# PowerSupply.net
KiCad netlist of a schematic drawn in Altium Designer
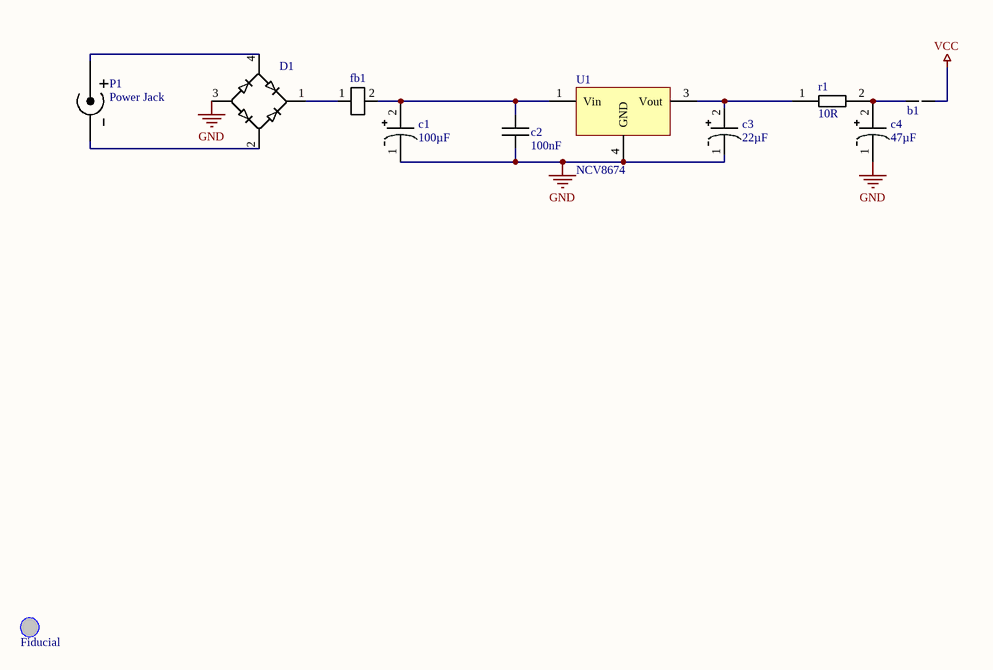
[diagram p0: PowerSupply.SchDoc]

(export (version "E")
  (design (tool "Eeschema 10.0.6"))
  (components
    (comp (ref "b1")
      (value "Solder Bridge")
      (footprint "Solder Bridge")
      (libsource (lib "Board_Props") (part "Solder Bridge"))
    )
    (comp (ref "c1")
      (value "100µF")
      (footprint "Elco-D")
      (description "Elco size D 6.3x5.4")
      (libsource (lib "Panasonic") (part "Elco D"))
    )
    (comp (ref "c2")
      (value "100nF")
      (footprint "0805")
      (description "...F")
      (libsource (lib "Generic R-C") (part "0805 Capacitor"))
    )
    (comp (ref "c3")
      (value "22µF")
      (footprint "Elco-D")
      (description "Elco size D 6.3x5.4")
      (libsource (lib "") (part "Elco D_1"))
    )
    (comp (ref "c4")
      (value "47µF")
      (footprint "Elco-D")
      (description "Elco size D 6.3x5.4")
      (libsource (lib "Panasonic") (part "Elco D"))
    )
    (comp (ref "D1")
      (value "Bridge Rectifier")
      (footprint "SOT-143")
      (libsource (lib "Infinion") (part "Bridge Rectifier"))
    )
    (comp (ref "f1")
      (value "Fiducial")
      (footprint "Fiducial")
      (libsource (lib "Board_Props") (part "Fiducial"))
    )
    (comp (ref "fb1")
      (value "*")
      (footprint "0805")
      (description "Ferrite Bead")
      (libsource (lib "TDK") (part "Ferrite Bead 0805 Package"))
    )
    (comp (ref "P1")
      (value "Power Jack")
      (footprint "Power Jack")
      (description "DC Power Jack")
      (libsource (lib "Multicomp") (part "DC Power Jack"))
    )
    (comp (ref "r1")
      (value "10R")
      (footprint "0805")
      (description "0805 Resistor package")
      (libsource (lib "Generic R-C") (part "0805 Resistor"))
    )
    (comp (ref "U1")
      (value "NCV8674")
      (footprint "D²PAK 3")
      (description "Very Low Iq Low Dropout Linear Regualtor")
      (libsource (lib "ON Semiconductor") (part "NCV8674"))
    )
  )
  (nets
    (net (code "1") (name "GND") (class "Default")
      (node (ref "D1") (pin "3") (pinfunction "3_3") (pintype "power_in"))
      (node (ref "U1") (pin "4") (pinfunction "GND_4") (pintype "power_in"))
      (node (ref "c1") (pin "1") (pintype "passive"))
      (node (ref "c2") (pin "1") (pintype "passive"))
      (node (ref "c3") (pin "1") (pintype "passive"))
      (node (ref "c4") (pin "1") (pintype "passive"))
    )
    (net (code "2") (name "Net-(D1-Pad1)") (class "Default")
      (node (ref "D1") (pin "1") (pinfunction "1_1") (pintype "power_in"))
      (node (ref "fb1") (pin "1") (pintype "passive"))
    )
    (net (code "3") (name "Net-(P1-GND)") (class "Default")
      (node (ref "D1") (pin "2") (pinfunction "2_2") (pintype "power_in"))
      (node (ref "P1") (pin "2") (pinfunction "GND_2") (pintype "power_in"))
    )
    (net (code "4") (name "Net-(P1-V+)") (class "Default")
      (node (ref "D1") (pin "4") (pinfunction "4_4") (pintype "power_in"))
      (node (ref "P1") (pin "1") (pinfunction "V+_1") (pintype "power_in"))
    )
    (net (code "5") (name "Net-(U1-Vin)") (class "Default")
      (node (ref "U1") (pin "1") (pinfunction "Vin_1") (pintype "power_in"))
      (node (ref "c1") (pin "2") (pintype "passive"))
      (node (ref "c2") (pin "2") (pintype "passive"))
      (node (ref "fb1") (pin "2") (pintype "passive"))
    )
    (net (code "6") (name "Net-(U1-Vout)") (class "Default")
      (node (ref "U1") (pin "3") (pinfunction "Vout_3") (pintype "power_in"))
      (node (ref "c3") (pin "2") (pintype "passive"))
      (node (ref "r1") (pin "1") (pintype "passive"))
    )
    (net (code "7") (name "Net-(b1-Pad1)") (class "Default")
      (node (ref "b1") (pin "1") (pinfunction "1_1") (pintype "passive"))
      (node (ref "c4") (pin "2") (pintype "passive"))
      (node (ref "r1") (pin "2") (pintype "passive"))
    )
    (net (code "8") (name "VCC") (class "Default")
      (node (ref "b1") (pin "2") (pinfunction "2_2") (pintype "passive"))
    )
  )
)
